# Sheet1.net
KiCad netlist of a schematic drawn in Altium Designer
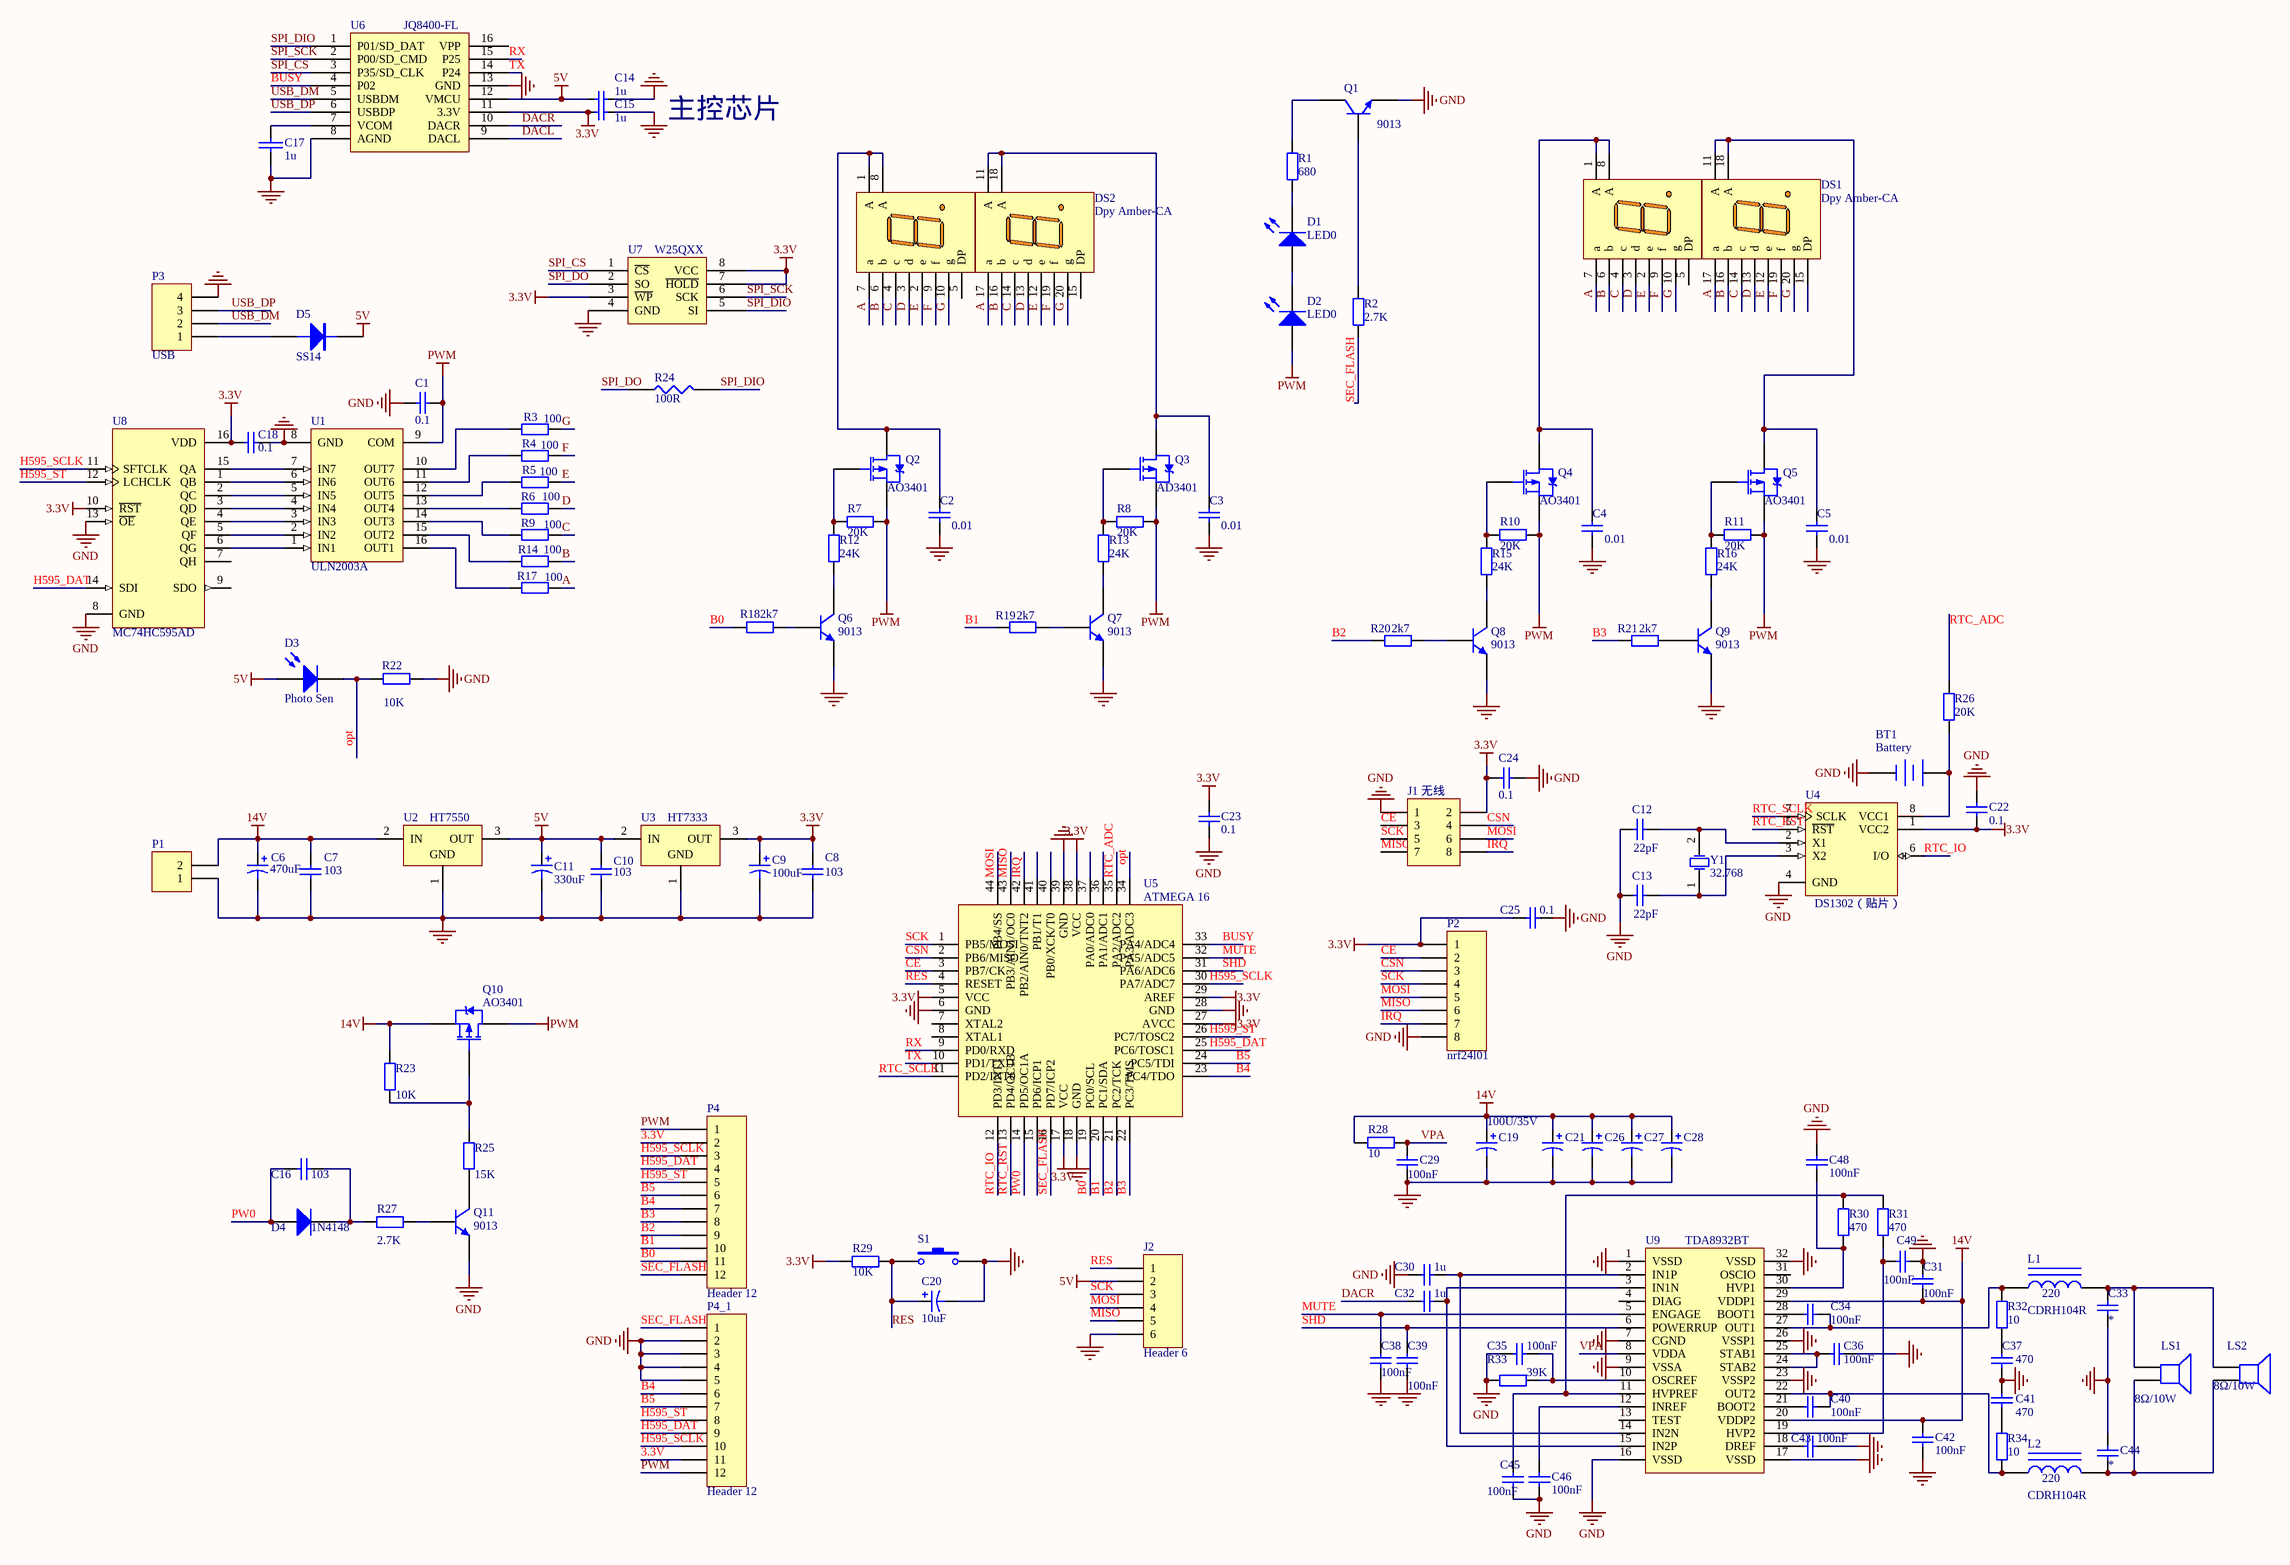
[diagram p0: Sheet1.SchDoc]

(export (version "E")
  (design (tool "Eeschema 10.0.6"))
  (components
    (comp (ref "BT1")
      (value "Battery")
      (footprint "1220电池底座")
      (description "Multicell Battery")
      (fields (field (name "PUBLISHER") "Altium Limited"))
      (libsource (lib "Miscellaneous Devices") (part "Battery"))
    )
    (comp (ref "C1")
      (value "0.1")
      (footprint "0805")
      (description "Capacitor")
      (fields (field (name "PUBLISHER") "Altium Limited"))
      (libsource (lib "Miscellaneous Devices") (part "Cap"))
    )
    (comp (ref "C2")
      (value "0.01")
      (footprint "0805")
      (description "Capacitor")
      (fields (field (name "Comment") "0.1") (field (name "PUBLISHER") "Altium Limited"))
      (libsource (lib "Miscellaneous Devices") (part "Cap"))
    )
    (comp (ref "C3")
      (value "0.01")
      (footprint "0805")
      (description "Capacitor")
      (fields (field (name "Comment") "0.1") (field (name "PUBLISHER") "Altium Limited"))
      (libsource (lib "Miscellaneous Devices") (part "Cap"))
    )
    (comp (ref "C4")
      (value "0.01")
      (footprint "0805")
      (description "Capacitor")
      (fields (field (name "Comment") "0.1") (field (name "PUBLISHER") "Altium Limited"))
      (libsource (lib "Miscellaneous Devices") (part "Cap"))
    )
    (comp (ref "C5")
      (value "0.01")
      (footprint "0805")
      (description "Capacitor")
      (fields (field (name "Comment") "0.1") (field (name "PUBLISHER") "Altium Limited"))
      (libsource (lib "Miscellaneous Devices") (part "Cap"))
    )
    (comp (ref "C6")
      (value "470uF")
      (footprint "470uf35V贴片")
      (description "Polarized Capacitor (Radial)")
      (fields (field (name "Comment") "Cap Pol1") (field (name "PUBLISHER") "Altium Limited"))
      (libsource (lib "Miscellaneous Devices") (part "Cap Pol1"))
    )
    (comp (ref "C7")
      (value "103")
      (footprint "0805")
      (description "Capacitor (Semiconductor SIM Model)")
      (fields (field (name "Comment") "Cap Semi") (field (name "PUBLISHER") "Altium Limited"))
      (libsource (lib "Miscellaneous Devices") (part "Cap Semi"))
    )
    (comp (ref "C8")
      (value "103")
      (footprint "0805")
      (description "Capacitor (Semiconductor SIM Model)")
      (fields (field (name "Comment") "Cap Semi") (field (name "PUBLISHER") "Altium Limited"))
      (libsource (lib "Miscellaneous Devices") (part "Cap Semi"))
    )
    (comp (ref "C9")
      (value "100uF")
      (footprint "1206")
      (description "Polarized Capacitor (Radial)")
      (fields (field (name "Comment") "Cap Pol1") (field (name "PUBLISHER") "Altium Limited"))
      (libsource (lib "Miscellaneous Devices") (part "Cap Pol1"))
    )
    (comp (ref "C10")
      (value "103")
      (footprint "0805")
      (description "Capacitor (Semiconductor SIM Model)")
      (fields (field (name "Comment") "Cap Semi") (field (name "PUBLISHER") "Altium Limited"))
      (libsource (lib "Miscellaneous Devices") (part "Cap Semi"))
    )
    (comp (ref "C11")
      (value "330uF")
      (footprint "220uf16V贴片")
      (description "Polarized Capacitor (Radial)")
      (fields (field (name "Comment") "Cap Pol1") (field (name "PUBLISHER") "Altium Limited"))
      (libsource (lib "Miscellaneous Devices") (part "Cap Pol1"))
    )
    (comp (ref "C12")
      (value "22pF")
      (footprint "0805")
      (description "Capacitor")
      (fields (field (name "Comment") "Cap") (field (name "PUBLISHER") "Altium Limited"))
      (libsource (lib "Miscellaneous Devices") (part "Cap"))
    )
    (comp (ref "C13")
      (value "22pF")
      (footprint "0805")
      (description "Capacitor")
      (fields (field (name "Comment") "Cap") (field (name "PUBLISHER") "Altium Limited"))
      (libsource (lib "Miscellaneous Devices") (part "Cap"))
    )
    (comp (ref "C14")
      (value "1u")
      (footprint "0805")
      (description "Capacitor")
      (libsource (lib "*") (part "CAP"))
    )
    (comp (ref "C15")
      (value "1u")
      (footprint "0805")
      (description "Capacitor")
      (libsource (lib "*") (part "CAP"))
    )
    (comp (ref "C16")
      (value "103")
      (footprint "0805")
      (description "Capacitor (Semiconductor SIM Model)")
      (fields (field (name "Comment") "Cap Semi") (field (name "PUBLISHER") "Altium Limited"))
      (libsource (lib "Miscellaneous Devices") (part "Cap Semi"))
    )
    (comp (ref "C17")
      (value "1u")
      (footprint "0805")
      (description "Capacitor")
      (libsource (lib "") (part "CAP_1"))
    )
    (comp (ref "C18")
      (value "0.1")
      (footprint "0805")
      (description "Capacitor")
      (fields (field (name "PUBLISHER") "Altium Limited"))
      (libsource (lib "Miscellaneous Devices") (part "Cap"))
    )
    (comp (ref "C19")
      (value "100U/35V")
      (footprint "220uf16V贴片")
      (description "Polarized Capacitor (Radial)")
      (fields (field (name "PUBLISHER") "Altium Limited"))
      (libsource (lib "Miscellaneous Devices") (part "Cap Pol1"))
    )
    (comp (ref "C20")
      (value "10uF")
      (footprint "1206")
      (description "Polarized Capacitor (Surface Mount)")
      (fields (field (name "PUBLISHER") "Altium Limited"))
      (libsource (lib "Miscellaneous Devices") (part "Cap Pol3"))
    )
    (comp (ref "C21")
      (value "Cap Pol1")
      (footprint "220uf16V贴片")
      (description "Polarized Capacitor (Radial)")
      (fields (field (name "PUBLISHER") "Altium Limited"))
      (libsource (lib "Miscellaneous Devices") (part "Cap Pol1"))
    )
    (comp (ref "C22")
      (value "0.1")
      (footprint "0805")
      (description "Capacitor")
      (fields (field (name "PUBLISHER") "Altium Limited"))
      (libsource (lib "Miscellaneous Devices") (part "Cap"))
    )
    (comp (ref "C23")
      (value "0.1")
      (footprint "0805")
      (description "Capacitor")
      (fields (field (name "PUBLISHER") "Altium Limited"))
      (libsource (lib "Miscellaneous Devices") (part "Cap"))
    )
    (comp (ref "C24")
      (value "0.1")
      (footprint "0805")
      (description "Capacitor")
      (fields (field (name "PUBLISHER") "Altium Limited"))
      (libsource (lib "Miscellaneous Devices") (part "Cap"))
    )
    (comp (ref "C25")
      (value "0.1")
      (footprint "0805")
      (description "Capacitor")
      (fields (field (name "PUBLISHER") "Altium Limited"))
      (libsource (lib "Miscellaneous Devices") (part "Cap"))
    )
    (comp (ref "C26")
      (value "Cap Pol1")
      (footprint "220uf16V贴片")
      (description "Polarized Capacitor (Radial)")
      (fields (field (name "PUBLISHER") "Altium Limited"))
      (libsource (lib "Miscellaneous Devices") (part "Cap Pol1"))
    )
    (comp (ref "C27")
      (value "Cap Pol1")
      (footprint "220uf16V贴片")
      (description "Polarized Capacitor (Radial)")
      (fields (field (name "PUBLISHER") "Altium Limited"))
      (libsource (lib "Miscellaneous Devices") (part "Cap Pol1"))
    )
    (comp (ref "C28")
      (value "Cap Pol1")
      (footprint "220uf16V贴片")
      (description "Polarized Capacitor (Radial)")
      (fields (field (name "PUBLISHER") "Altium Limited"))
      (libsource (lib "Miscellaneous Devices") (part "Cap Pol1"))
    )
    (comp (ref "C29")
      (value "100nF")
      (footprint "0603")
      (description "Capacitor")
      (fields (field (name "Comment") "0.1") (field (name "PUBLISHER") "Altium Limited"))
      (libsource (lib "Miscellaneous Devices") (part "Cap"))
    )
    (comp (ref "C30")
      (value "1u")
      (footprint "0603")
      (description "Capacitor")
      (fields (field (name "Comment") "0.1") (field (name "PUBLISHER") "Altium Limited"))
      (libsource (lib "Miscellaneous Devices") (part "Cap"))
    )
    (comp (ref "C31")
      (value "100nF")
      (footprint "0603")
      (description "Capacitor")
      (fields (field (name "Comment") "0.1") (field (name "PUBLISHER") "Altium Limited"))
      (libsource (lib "Miscellaneous Devices") (part "Cap"))
    )
    (comp (ref "C32")
      (value "1u")
      (footprint "0603")
      (description "Capacitor")
      (fields (field (name "Comment") "0.1") (field (name "PUBLISHER") "Altium Limited"))
      (libsource (lib "Miscellaneous Devices") (part "Cap"))
    )
    (comp (ref "C33")
      (value "0.1")
      (footprint "0805")
      (description "Capacitor")
      (fields (field (name "ALTIUM_VALUE") "*") (field (name "PUBLISHER") "Altium Limited"))
      (libsource (lib "Miscellaneous Devices") (part "Cap"))
    )
    (comp (ref "C34")
      (value "100nF")
      (footprint "0603")
      (description "Capacitor")
      (fields (field (name "Comment") "0.1") (field (name "PUBLISHER") "Altium Limited"))
      (libsource (lib "Miscellaneous Devices") (part "Cap"))
    )
    (comp (ref "C35")
      (value "100nF")
      (footprint "0603")
      (description "Capacitor")
      (fields (field (name "Comment") "0.1") (field (name "PUBLISHER") "Altium Limited"))
      (libsource (lib "Miscellaneous Devices") (part "Cap"))
    )
    (comp (ref "C36")
      (value "100nF")
      (footprint "0603")
      (description "Capacitor")
      (fields (field (name "Comment") "0.1") (field (name "PUBLISHER") "Altium Limited"))
      (libsource (lib "Miscellaneous Devices") (part "Cap"))
    )
    (comp (ref "C37")
      (value "470")
      (footprint "0603")
      (description "Capacitor")
      (fields (field (name "Comment") "0.1") (field (name "PUBLISHER") "Altium Limited"))
      (libsource (lib "Miscellaneous Devices") (part "Cap"))
    )
    (comp (ref "C38")
      (value "100nF")
      (footprint "0603")
      (description "Capacitor")
      (fields (field (name "Comment") "0.1") (field (name "PUBLISHER") "Altium Limited"))
      (libsource (lib "Miscellaneous Devices") (part "Cap"))
    )
    (comp (ref "C39")
      (value "100nF")
      (footprint "0603")
      (description "Capacitor")
      (fields (field (name "Comment") "0.1") (field (name "PUBLISHER") "Altium Limited"))
      (libsource (lib "Miscellaneous Devices") (part "Cap"))
    )
    (comp (ref "C40")
      (value "100nF")
      (footprint "0603")
      (description "Capacitor")
      (fields (field (name "Comment") "0.1") (field (name "PUBLISHER") "Altium Limited"))
      (libsource (lib "Miscellaneous Devices") (part "Cap"))
    )
    (comp (ref "C41")
      (value "470")
      (footprint "0603")
      (description "Capacitor")
      (fields (field (name "Comment") "0.1") (field (name "PUBLISHER") "Altium Limited"))
      (libsource (lib "Miscellaneous Devices") (part "Cap"))
    )
    (comp (ref "C42")
      (value "100nF")
      (footprint "0603")
      (description "Capacitor")
      (fields (field (name "Comment") "0.1") (field (name "PUBLISHER") "Altium Limited"))
      (libsource (lib "Miscellaneous Devices") (part "Cap"))
    )
    (comp (ref "C43")
      (value "100nF")
      (footprint "0603")
      (description "Capacitor")
      (fields (field (name "Comment") "0.1") (field (name "PUBLISHER") "Altium Limited"))
      (libsource (lib "Miscellaneous Devices") (part "Cap"))
    )
    (comp (ref "C44")
      (value "0.1")
      (footprint "0805")
      (description "Capacitor")
      (fields (field (name "ALTIUM_VALUE") "*") (field (name "PUBLISHER") "Altium Limited"))
      (libsource (lib "Miscellaneous Devices") (part "Cap"))
    )
    (comp (ref "C45")
      (value "100nF")
      (footprint "0603")
      (description "Capacitor")
      (fields (field (name "Comment") "0.1") (field (name "PUBLISHER") "Altium Limited"))
      (libsource (lib "Miscellaneous Devices") (part "Cap"))
    )
    (comp (ref "C46")
      (value "100nF")
      (footprint "0603")
      (description "Capacitor")
      (fields (field (name "Comment") "0.1") (field (name "PUBLISHER") "Altium Limited"))
      (libsource (lib "Miscellaneous Devices") (part "Cap"))
    )
    (comp (ref "C48")
      (value "100nF")
      (footprint "0603")
      (description "Capacitor")
      (fields (field (name "Comment") "0.1") (field (name "PUBLISHER") "Altium Limited"))
      (libsource (lib "Miscellaneous Devices") (part "Cap"))
    )
    (comp (ref "C49")
      (value "100nF")
      (footprint "0603")
      (description "Capacitor")
      (fields (field (name "Comment") "0.1") (field (name "PUBLISHER") "Altium Limited"))
      (libsource (lib "Miscellaneous Devices") (part "Cap"))
    )
    (comp (ref "D1")
      (value "LED0")
      (footprint "led")
      (description "Typical INFRARED GaAs LED")
      (fields (field (name "PUBLISHER") "Altium Limited"))
      (libsource (lib "Miscellaneous Devices") (part "LED0"))
    )
    (comp (ref "D2")
      (value "LED0")
      (footprint "led")
      (description "Typical INFRARED GaAs LED")
      (fields (field (name "PUBLISHER") "Altium Limited"))
      (libsource (lib "Miscellaneous Devices") (part "LED0"))
    )
    (comp (ref "D3")
      (value "Photo Sen")
      (footprint "2排针")
      (description "Photosensitive Diode")
      (fields (field (name "PUBLISHER") "Altium Limited"))
      (libsource (lib "Miscellaneous Devices") (part "Photo Sen"))
    )
    (comp (ref "D4")
      (value "1N4148")
      (footprint "1206")
      (description "1 Amp General Purpose Rectifier")
      (fields (field (name "PUBLISHER") "Altium Limited"))
      (libsource (lib "Miscellaneous Devices") (part "Diode 1N4007"))
    )
    (comp (ref "D5")
      (value "SS14")
      (footprint "1206")
      (description "Diode")
      (libsource (lib "*") (part "DIODE"))
    )
    (comp (ref "DS1")
      (value "Dpy Amber-CA")
      (footprint "5英寸数码管")
      (description "7.62 mm Black Surface Orange 7-Segment Display: CA, RH DP")
      (fields (field (name "PUBLISHER") "Altium Limited"))
      (libsource (lib "PCB_Project1") (part "Dpy Amber-CA"))
    )
    (comp (ref "DS2")
      (value "Dpy Amber-CA")
      (footprint "5英寸数码管")
      (description "7.62 mm Black Surface Orange 7-Segment Display: CA, RH DP")
      (fields (field (name "PUBLISHER") "Altium Limited"))
      (libsource (lib "PCB_Project1") (part "Dpy Amber-CA"))
    )
    (comp (ref "J1")
      (value "无线")
      (footprint "无线模块")
      (description "Header, 4-Pin, Dual row")
      (fields (field (name "PUBLISHER") "Altium Limited"))
      (libsource (lib "Miscellaneous Connectors") (part "Header 4X2"))
    )
    (comp (ref "J2")
      (value "Header 6")
      (footprint "HDR1X6")
      (description "Header, 6-Pin")
      (fields (field (name "PUBLISHER") "Altium Limited"))
      (libsource (lib "Miscellaneous Connectors") (part "Header 6"))
    )
    (comp (ref "L1")
      (value "220")
      (footprint "CDRH104")
      (description "Magnetic-Core Inductor")
      (fields (field (name "ALTIUM_VALUE") "CDRH104R") (field (name "PUBLISHER") "Altium Limited"))
      (libsource (lib "Miscellaneous Devices") (part "Inductor Iron"))
    )
    (comp (ref "L2")
      (value "220")
      (footprint "CDRH104")
      (description "Magnetic-Core Inductor")
      (fields (field (name "ALTIUM_VALUE") "CDRH104R") (field (name "PUBLISHER") "Altium Limited"))
      (libsource (lib "Miscellaneous Devices") (part "Inductor Iron"))
    )
    (comp (ref "LS1")
      (value "8Ω/10W")
      (footprint "2排针")
      (description "Loudspeaker")
      (fields (field (name "PUBLISHER") "Altium Limited"))
      (libsource (lib "Miscellaneous Devices") (part "Speaker"))
    )
    (comp (ref "LS2")
      (value "8Ω/10W")
      (footprint "2排针")
      (description "Loudspeaker")
      (fields (field (name "PUBLISHER") "Altium Limited"))
      (libsource (lib "Miscellaneous Devices") (part "Speaker"))
    )
    (comp (ref "P1")
      (value "Header 2")
      (footprint "电源插头")
      (description "Header, 2-Pin")
      (fields (field (name "PUBLISHER") "Altium Limited"))
      (libsource (lib "Miscellaneous Connectors") (part "Header 2"))
    )
    (comp (ref "P2")
      (value "nrf24l01")
      (footprint "24L01")
      (description "Header, 8-Pin")
      (fields (field (name "PUBLISHER") "Altium Limited"))
      (libsource (lib "Miscellaneous Connectors") (part "Header 8"))
    )
    (comp (ref "P3")
      (value "USB")
      (footprint "HDR1X4")
      (description "Header, 4-Pin")
      (fields (field (name "PUBLISHER") "Altium Limited"))
      (libsource (lib "Miscellaneous Connectors") (part "Header 4"))
    )
    (comp (ref "P4")
      (value "Header 12")
      (footprint "FPC-12P1MM")
      (description "Header, 12-Pin")
      (fields (field (name "PUBLISHER") "Altium Limited"))
      (libsource (lib "Miscellaneous Connectors") (part "Header 12"))
    )
    (comp (ref "P4_1")
      (value "Header 12")
      (footprint "FPC-12P1MM")
      (description "Header, 12-Pin")
      (fields (field (name "PUBLISHER") "Altium Limited"))
      (libsource (lib "Miscellaneous Connectors") (part "Header 12"))
    )
    (comp (ref "Q1")
      (value "9013")
      (footprint "9013贴片（专用）")
      (description "NPN General Purpose Amplifier")
      (fields (field (name "PUBLISHER") "Altium Limited"))
      (libsource (lib "") (part "2N3904_1"))
    )
    (comp (ref "Q2")
      (value "AO3401")
      (footprint "SOP-23")
      (description "P-Channel Power MOSFET")
      (fields (field (name "PUBLISHER") "Altium Limited"))
      (libsource (lib "Miscellaneous Devices") (part "PMOS-2"))
    )
    (comp (ref "Q3")
      (value "AD3401")
      (footprint "SOP-23")
      (description "P-Channel Power MOSFET")
      (fields (field (name "PUBLISHER") "Altium Limited"))
      (libsource (lib "Miscellaneous Devices") (part "PMOS-2"))
    )
    (comp (ref "Q4")
      (value "AO3401")
      (footprint "SOP-23")
      (description "P-Channel Power MOSFET")
      (fields (field (name "PUBLISHER") "Altium Limited"))
      (libsource (lib "Miscellaneous Devices") (part "PMOS-2"))
    )
    (comp (ref "Q5")
      (value "AO3401")
      (footprint "SOP-23")
      (description "P-Channel Power MOSFET")
      (fields (field (name "PUBLISHER") "Altium Limited"))
      (libsource (lib "Miscellaneous Devices") (part "PMOS-2"))
    )
    (comp (ref "Q6")
      (value "9013")
      (footprint "9013贴片（专用）")
      (description "NPN General Purpose Amplifier")
      (fields (field (name "PUBLISHER") "Altium Limited"))
      (libsource (lib "Miscellaneous Devices") (part "2N3904"))
    )
    (comp (ref "Q7")
      (value "9013")
      (footprint "9013贴片（专用）")
      (description "NPN General Purpose Amplifier")
      (fields (field (name "PUBLISHER") "Altium Limited"))
      (libsource (lib "Miscellaneous Devices") (part "2N3904"))
    )
    (comp (ref "Q8")
      (value "9013")
      (footprint "9013贴片（专用）")
      (description "NPN General Purpose Amplifier")
      (fields (field (name "PUBLISHER") "Altium Limited"))
      (libsource (lib "Miscellaneous Devices") (part "2N3904"))
    )
    (comp (ref "Q9")
      (value "9013")
      (footprint "9013贴片（专用）")
      (description "NPN General Purpose Amplifier")
      (fields (field (name "PUBLISHER") "Altium Limited"))
      (libsource (lib "Miscellaneous Devices") (part "2N3904"))
    )
    (comp (ref "Q10")
      (value "AO3401")
      (footprint "SOP-23")
      (description "P-Channel Power MOSFET")
      (fields (field (name "PUBLISHER") "Altium Limited"))
      (libsource (lib "") (part "PMOS-2_1"))
    )
    (comp (ref "Q11")
      (value "9013")
      (footprint "9013贴片（专用）")
      (description "NPN General Purpose Amplifier")
      (fields (field (name "PUBLISHER") "Altium Limited"))
      (libsource (lib "") (part "2N3904_1"))
    )
    (comp (ref "R1")
      (value "680")
      (footprint "0805")
      (description "Resistor")
      (fields (field (name "Comment") "Res2") (field (name "PUBLISHER") "Altium Limited"))
      (libsource (lib "Miscellaneous Devices") (part "Res2"))
    )
    (comp (ref "R2")
      (value "2.7K")
      (footprint "0805")
      (description "Resistor")
      (fields (field (name "Comment") "Res2") (field (name "PUBLISHER") "Altium Limited"))
      (libsource (lib "Miscellaneous Devices") (part "Res2"))
    )
    (comp (ref "R3")
      (value "100")
      (footprint "0805")
      (description "Resistor")
      (fields (field (name "PUBLISHER") "Altium Limited"))
      (libsource (lib "") (part "Res2_2"))
    )
    (comp (ref "R4")
      (value "100")
      (footprint "0805")
      (description "Resistor")
      (fields (field (name "PUBLISHER") "Altium Limited"))
      (libsource (lib "") (part "Res2_2"))
    )
    (comp (ref "R5")
      (value "100")
      (footprint "0805")
      (description "Resistor")
      (fields (field (name "PUBLISHER") "Altium Limited"))
      (libsource (lib "") (part "Res2_2"))
    )
    (comp (ref "R6")
      (value "100")
      (footprint "0805")
      (description "Resistor")
      (fields (field (name "PUBLISHER") "Altium Limited"))
      (libsource (lib "") (part "Res2_2"))
    )
    (comp (ref "R7")
      (value "20K")
      (footprint "0805")
      (description "Resistor")
      (fields (field (name "PUBLISHER") "Altium Limited"))
      (libsource (lib "") (part "Res2_1"))
    )
    (comp (ref "R8")
      (value "20K")
      (footprint "0805")
      (description "Resistor")
      (fields (field (name "PUBLISHER") "Altium Limited"))
      (libsource (lib "") (part "Res2_1"))
    )
    (comp (ref "R9")
      (value "100")
      (footprint "0805")
      (description "Resistor")
      (fields (field (name "PUBLISHER") "Altium Limited"))
      (libsource (lib "") (part "Res2_2"))
    )
    (comp (ref "R10")
      (value "20K")
      (footprint "0805")
      (description "Resistor")
      (fields (field (name "PUBLISHER") "Altium Limited"))
      (libsource (lib "") (part "Res2_1"))
    )
    (comp (ref "R11")
      (value "20K")
      (footprint "0805")
      (description "Resistor")
      (fields (field (name "PUBLISHER") "Altium Limited"))
      (libsource (lib "") (part "Res2_1"))
    )
    (comp (ref "R12")
      (value "24K")
      (footprint "0805")
      (description "Resistor")
      (fields (field (name "PUBLISHER") "Altium Limited"))
      (libsource (lib "") (part "Res2_4"))
    )
    (comp (ref "R13")
      (value "24K")
      (footprint "0603")
      (description "Resistor")
      (fields (field (name "PUBLISHER") "Altium Limited"))
      (libsource (lib "") (part "Res2_4"))
    )
    (comp (ref "R14")
      (value "100")
      (footprint "0805")
      (description "Resistor")
      (fields (field (name "PUBLISHER") "Altium Limited"))
      (libsource (lib "") (part "Res2_2"))
    )
    (comp (ref "R15")
      (value "24K")
      (footprint "0805")
      (description "Resistor")
      (fields (field (name "PUBLISHER") "Altium Limited"))
      (libsource (lib "") (part "Res2_4"))
    )
    (comp (ref "R16")
      (value "24K")
      (footprint "0805")
      (description "Resistor")
      (fields (field (name "PUBLISHER") "Altium Limited"))
      (libsource (lib "") (part "Res2_4"))
    )
    (comp (ref "R17")
      (value "100")
      (footprint "0805")
      (description "Resistor")
      (fields (field (name "PUBLISHER") "Altium Limited"))
      (libsource (lib "") (part "Res2_2"))
    )
    (comp (ref "R18")
      (value "2k7")
      (footprint "0805")
      (description "Resistor")
      (fields (field (name "PUBLISHER") "Altium Limited"))
      (libsource (lib "") (part "Res2_2"))
    )
    (comp (ref "R19")
      (value "2k7")
      (footprint "0805")
      (description "Resistor")
      (fields (field (name "PUBLISHER") "Altium Limited"))
      (libsource (lib "") (part "Res2_2"))
    )
    (comp (ref "R20")
      (value "2k7")
      (footprint "0805")
      (description "Resistor")
      (fields (field (name "PUBLISHER") "Altium Limited"))
      (libsource (lib "") (part "Res2_2"))
    )
    (comp (ref "R21")
      (value "2k7")
      (footprint "0805")
      (description "Resistor")
      (fields (field (name "PUBLISHER") "Altium Limited"))
      (libsource (lib "") (part "Res2_2"))
    )
    (comp (ref "R22")
      (value "10K")
      (footprint "0805")
      (description "Resistor")
      (fields (field (name "PUBLISHER") "Altium Limited"))
      (libsource (lib "") (part "Res2_6"))
    )
    (comp (ref "R23")
      (value "10K")
      (footprint "0805")
      (description "Resistor")
      (fields (field (name "Comment") "Res2") (field (name "PUBLISHER") "Altium Limited"))
      (libsource (lib "Miscellaneous Devices") (part "Res2"))
    )
    (comp (ref "R24") (value "100R") (libsource (lib "*") (part "RES1")))
    (comp (ref "R25")
      (value "15K")
      (footprint "0805")
      (description "Resistor")
      (fields (field (name "Comment") "Res2") (field (name "PUBLISHER") "Altium Limited"))
      (libsource (lib "Miscellaneous Devices") (part "Res2"))
    )
    (comp (ref "R26")
      (value "20K")
      (footprint "0805")
      (description "Resistor")
      (fields (field (name "PUBLISHER") "Altium Limited"))
      (libsource (lib "") (part "Res2_4"))
    )
    (comp (ref "R27")
      (value "2.7K")
      (footprint "0805")
      (description "Resistor")
      (fields (field (name "Comment") "Res2") (field (name "PUBLISHER") "Altium Limited"))
      (libsource (lib "") (part "Res2_6"))
    )
    (comp (ref "R28")
      (value "10")
      (footprint "0805")
      (description "Resistor")
      (fields (field (name "PUBLISHER") "Altium Limited"))
      (libsource (lib "Miscellaneous Devices") (part "Res2"))
    )
    (comp (ref "R29")
      (value "10K")
      (footprint "0805")
      (description "Resistor")
      (fields (field (name "PUBLISHER") "Altium Limited"))
      (libsource (lib "") (part "Res2_3"))
    )
    (comp (ref "R30")
      (value "470")
      (footprint "0603")
      (description "Resistor")
      (fields (field (name "PUBLISHER") "Altium Limited"))
      (libsource (lib "") (part "Res2_4"))
    )
    (comp (ref "R31")
      (value "470")
      (footprint "0603")
      (description "Resistor")
      (fields (field (name "PUBLISHER") "Altium Limited"))
      (libsource (lib "") (part "Res2_4"))
    )
    (comp (ref "R32")
      (value "10")
      (footprint "0603")
      (description "Resistor")
      (fields (field (name "PUBLISHER") "Altium Limited"))
      (libsource (lib "") (part "Res2_4"))
    )
    (comp (ref "R33")
      (value "39K")
      (footprint "0603")
      (description "Resistor")
      (fields (field (name "PUBLISHER") "Altium Limited"))
      (libsource (lib "") (part "Res2_1"))
    )
    (comp (ref "R34")
      (value "10")
      (footprint "0603")
      (description "Resistor")
      (fields (field (name "PUBLISHER") "Altium Limited"))
      (libsource (lib "") (part "Res2_5"))
    )
    (comp (ref "S1")
      (value "~")
      (footprint "4脚按键")
      (description "Switch")
      (fields (field (name "PUBLISHER") "Altium Limited"))
      (libsource (lib "Miscellaneous Devices") (part "SW-PB"))
    )
    (comp (ref "U1")
      (value "ULN2003A")
      (footprint "SO-16")
      (description "High-Voltage, High-Current Darlington Array")
      (fields (field (name "PUBLISHER") "Altium Limited"))
      (libsource (lib "Allegro Interface Darlington Driver") (part "ULN2003A"))
    )
    (comp (ref "U2")
      (value "HT7550")
      (footprint "SOT89L")
      (description "3.0V 100mA Low Power,  Low Dropout Voltage (LDO) Regulator")
      (fields (field (name "PUBLISHER") "Altium Limited"))
      (libsource (lib "Holtek Power Mgt Voltage Regulator") (part "HT7530-1"))
    )
    (comp (ref "U3")
      (value "HT7333")
      (footprint "SOT89L")
      (description "3.0V 100mA Low Power,  Low Dropout Voltage (LDO) Regulator")
      (fields (field (name "PUBLISHER") "Altium Limited"))
      (libsource (lib "Holtek Power Mgt Voltage Regulator") (part "HT7530-1"))
    )
    (comp (ref "U4")
      (value "DS1302（贴片）")
      (footprint "SOP8（DS1302）")
      (description "Trickle Charge Timekeeping Chip")
      (fields (field (name "PUBLISHER") "Altium Limited"))
      (libsource (lib "Dallas Peripheral Real Time Clock") (part "DS1302"))
    )
    (comp (ref "U5")
      (value "ATMEGA 16")
      (footprint "44贴片（顶层）")
      (libsource (lib "AVR最小系统") (part "ATMEGA 16"))
    )
    (comp (ref "U6") (value "JQ8400-FL") (footprint "SO-16") (libsource (lib "*") (part "W6082")))
    (comp (ref "U7") (value "W25QXX") (footprint "w25") (libsource (lib "*") (part "W25QXX")))
    (comp (ref "U8")
      (value "MC74HC595AD")
      (footprint "751B-05_N")
      (description "8-Bit Serial-Input/Serial or Prallel-Output Shift Register with Latched 3-State Outputs")
      (fields (field (name "PUBLISHER") "Altium Limited"))
      (libsource (lib "ON Semi Logic Register") (part "MC74HC595AD"))
    )
    (comp (ref "U9")
      (value "TDA8932BT")
      (footprint "SOIC127P1047-32L")
      (libsource (lib "PCB_Project1") (part "TDA8932"))
    )
    (comp (ref "Y1")
      (value "32.768")
      (footprint "32K")
      (description "Crystal Oscillator")
      (fields (field (name "PUBLISHER") "Altium Limited"))
      (libsource (lib "Miscellaneous Devices") (part "XTAL"))
    )
  )
  (nets
    (net (code "1") (name "/A") (class "Default")
      (node (ref "DS1") (pin "17") (pinfunction "a_17") (pintype "passive"))
      (node (ref "DS1") (pin "7") (pinfunction "a_7") (pintype "passive"))
      (node (ref "DS2") (pin "17") (pinfunction "a_17") (pintype "passive"))
      (node (ref "DS2") (pin "7") (pinfunction "a_7") (pintype "passive"))
      (node (ref "R17") (pin "1") (pinfunction "1_1") (pintype "passive"))
    )
    (net (code "2") (name "/B") (class "Default")
      (node (ref "DS1") (pin "16") (pinfunction "b_16") (pintype "passive"))
      (node (ref "DS1") (pin "6") (pinfunction "b_6") (pintype "passive"))
      (node (ref "DS2") (pin "16") (pinfunction "b_16") (pintype "passive"))
      (node (ref "DS2") (pin "6") (pinfunction "b_6") (pintype "passive"))
      (node (ref "R14") (pin "1") (pinfunction "1_1") (pintype "passive"))
    )
    (net (code "3") (name "/B0") (class "Default")
      (node (ref "P4") (pin "11") (pinfunction "11_11") (pintype "passive"))
      (node (ref "R18") (pin "2") (pinfunction "2_2") (pintype "passive"))
      (node (ref "U5") (pin "19") (pinfunction "PC0/SCL_19") (pintype "passive"))
    )
    (net (code "4") (name "/B1") (class "Default")
      (node (ref "P4") (pin "10") (pinfunction "10_10") (pintype "passive"))
      (node (ref "R19") (pin "2") (pinfunction "2_2") (pintype "passive"))
      (node (ref "U5") (pin "20") (pinfunction "PC1/SDA_20") (pintype "passive"))
    )
    (net (code "5") (name "/B2") (class "Default")
      (node (ref "P4") (pin "9") (pinfunction "9_9") (pintype "passive"))
      (node (ref "R20") (pin "2") (pinfunction "2_2") (pintype "passive"))
      (node (ref "U5") (pin "21") (pinfunction "PC2/TCK_21") (pintype "passive"))
    )
    (net (code "6") (name "/B3") (class "Default")
      (node (ref "P4") (pin "8") (pinfunction "8_8") (pintype "passive"))
      (node (ref "R21") (pin "2") (pinfunction "2_2") (pintype "passive"))
      (node (ref "U5") (pin "22") (pinfunction "PC3/TMS_22") (pintype "passive"))
    )
    (net (code "7") (name "/B4") (class "Default")
      (node (ref "P4") (pin "7") (pinfunction "7_7") (pintype "passive"))
      (node (ref "P4_1") (pin "6") (pinfunction "6_6") (pintype "passive"))
      (node (ref "U5") (pin "23") (pinfunction "PC4/TDO_23") (pintype "passive"))
    )
    (net (code "8") (name "/B5") (class "Default")
      (node (ref "P4") (pin "6") (pinfunction "6_6") (pintype "passive"))
      (node (ref "P4_1") (pin "7") (pinfunction "7_7") (pintype "passive"))
      (node (ref "U5") (pin "24") (pinfunction "PC5/TDI_24") (pintype "passive"))
    )
    (net (code "9") (name "/BUSY") (class "Default")
      (node (ref "U5") (pin "33") (pinfunction "PA4/ADC4_33") (pintype "passive"))
      (node (ref "U6") (pin "4") (pinfunction "P02_4") (pintype "passive"))
    )
    (net (code "10") (name "/C") (class "Default")
      (node (ref "DS1") (pin "14") (pinfunction "c_14") (pintype "passive"))
      (node (ref "DS1") (pin "4") (pinfunction "c_4") (pintype "passive"))
      (node (ref "DS2") (pin "14") (pinfunction "c_14") (pintype "passive"))
      (node (ref "DS2") (pin "4") (pinfunction "c_4") (pintype "passive"))
      (node (ref "R9") (pin "1") (pinfunction "1_1") (pintype "passive"))
    )
    (net (code "11") (name "/CE") (class "Default")
      (node (ref "J1") (pin "3") (pinfunction "3_3") (pintype "passive"))
      (node (ref "P2") (pin "2") (pinfunction "2_2") (pintype "passive"))
      (node (ref "U5") (pin "3") (pinfunction "PB7/CK_3") (pintype "passive"))
    )
    (net (code "12") (name "/CSN") (class "Default")
      (node (ref "J1") (pin "4") (pinfunction "4_4") (pintype "passive"))
      (node (ref "P2") (pin "3") (pinfunction "3_3") (pintype "passive"))
      (node (ref "U5") (pin "2") (pinfunction "PB6/MISO_2") (pintype "passive"))
    )
    (net (code "13") (name "/D") (class "Default")
      (node (ref "DS1") (pin "13") (pinfunction "d_13") (pintype "passive"))
      (node (ref "DS1") (pin "3") (pinfunction "d_3") (pintype "passive"))
      (node (ref "DS2") (pin "13") (pinfunction "d_13") (pintype "passive"))
      (node (ref "DS2") (pin "3") (pinfunction "d_3") (pintype "passive"))
      (node (ref "R6") (pin "1") (pinfunction "1_1") (pintype "passive"))
    )
    (net (code "14") (name "/DACL") (class "Default")
      (node (ref "U6") (pin "9") (pinfunction "DACL_9") (pintype "passive"))
    )
    (net (code "15") (name "/DACR") (class "Default")
      (node (ref "C32") (pin "1") (pinfunction "1_1") (pintype "passive"))
      (node (ref "U6") (pin "10") (pinfunction "DACR_10") (pintype "passive"))
    )
    (net (code "16") (name "/E") (class "Default")
      (node (ref "DS1") (pin "12") (pinfunction "e_12") (pintype "passive"))
      (node (ref "DS1") (pin "2") (pinfunction "e_2") (pintype "passive"))
      (node (ref "DS2") (pin "12") (pinfunction "e_12") (pintype "passive"))
      (node (ref "DS2") (pin "2") (pinfunction "e_2") (pintype "passive"))
      (node (ref "R5") (pin "1") (pinfunction "1_1") (pintype "passive"))
    )
    (net (code "17") (name "/F") (class "Default")
      (node (ref "DS1") (pin "19") (pinfunction "f_19") (pintype "passive"))
      (node (ref "DS1") (pin "9") (pinfunction "f_9") (pintype "passive"))
      (node (ref "DS2") (pin "19") (pinfunction "f_19") (pintype "passive"))
      (node (ref "DS2") (pin "9") (pinfunction "f_9") (pintype "passive"))
      (node (ref "R4") (pin "1") (pinfunction "1_1") (pintype "passive"))
    )
    (net (code "18") (name "/G") (class "Default")
      (node (ref "DS1") (pin "10") (pinfunction "g_10") (pintype "passive"))
      (node (ref "DS1") (pin "20") (pinfunction "g_20") (pintype "passive"))
      (node (ref "DS2") (pin "10") (pinfunction "g_10") (pintype "passive"))
      (node (ref "DS2") (pin "20") (pinfunction "g_20") (pintype "passive"))
      (node (ref "R3") (pin "1") (pinfunction "1_1") (pintype "passive"))
    )
    (net (code "19") (name "/H595_DAT") (class "Default")
      (node (ref "P4") (pin "4") (pinfunction "4_4") (pintype "passive"))
      (node (ref "P4_1") (pin "9") (pinfunction "9_9") (pintype "passive"))
      (node (ref "U5") (pin "25") (pinfunction "PC6/TOSC1_25") (pintype "passive"))
      (node (ref "U8") (pin "14") (pinfunction "SDI_14") (pintype "input"))
    )
    (net (code "20") (name "/H595_SCLK") (class "Default")
      (node (ref "P4") (pin "3") (pinfunction "3_3") (pintype "passive"))
      (node (ref "P4_1") (pin "10") (pinfunction "10_10") (pintype "passive"))
      (node (ref "U5") (pin "30") (pinfunction "PA7/ADC7_30") (pintype "passive"))
      (node (ref "U8") (pin "11") (pinfunction "SFTCLK_11") (pintype "input"))
    )
    (net (code "21") (name "/H595_ST") (class "Default")
      (node (ref "P4") (pin "5") (pinfunction "5_5") (pintype "passive"))
      (node (ref "P4_1") (pin "8") (pinfunction "8_8") (pintype "passive"))
      (node (ref "U5") (pin "26") (pinfunction "PC7/TOSC2_26") (pintype "passive"))
      (node (ref "U8") (pin "12") (pinfunction "LCHCLK_12") (pintype "input"))
    )
    (net (code "22") (name "/IRQ") (class "Default")
      (node (ref "J1") (pin "8") (pinfunction "8_8") (pintype "passive"))
      (node (ref "P2") (pin "7") (pinfunction "7_7") (pintype "passive"))
      (node (ref "U5") (pin "42") (pinfunction "PB2/AIN0/TNT2_42") (pintype "passive"))
    )
    (net (code "23") (name "/MISO") (class "Default")
      (node (ref "J1") (pin "7") (pinfunction "7_7") (pintype "passive"))
      (node (ref "J2") (pin "5") (pinfunction "5_5") (pintype "passive"))
      (node (ref "P2") (pin "6") (pinfunction "6_6") (pintype "passive"))
      (node (ref "U5") (pin "43") (pinfunction "PB3/AIN1/OC0_43") (pintype "passive"))
    )
    (net (code "24") (name "/MOSI") (class "Default")
      (node (ref "J1") (pin "6") (pinfunction "6_6") (pintype "passive"))
      (node (ref "J2") (pin "4") (pinfunction "4_4") (pintype "passive"))
      (node (ref "P2") (pin "5") (pinfunction "5_5") (pintype "passive"))
      (node (ref "U5") (pin "44") (pinfunction "PB4/SS_44") (pintype "passive"))
    )
    (net (code "25") (name "/MUTE") (class "Default")
      (node (ref "C38") (pin "2") (pinfunction "2_2") (pintype "passive"))
      (node (ref "U5") (pin "32") (pinfunction "PA5/ADC5_32") (pintype "passive"))
      (node (ref "U9") (pin "5") (pinfunction "ENGAGE_5") (pintype "passive"))
    )
    (net (code "26") (name "/PW0") (class "Default")
      (node (ref "C16") (pin "2") (pinfunction "2_2") (pintype "passive"))
      (node (ref "D4") (pin "1") (pinfunction "A_1") (pintype "passive"))
      (node (ref "U5") (pin "14") (pinfunction "PD5/OC1A_14") (pintype "passive"))
    )
    (net (code "27") (name "/RES") (class "Default")
      (node (ref "C20") (pin "1") (pinfunction "1_1") (pintype "passive"))
      (node (ref "J2") (pin "1") (pinfunction "1_1") (pintype "passive"))
      (node (ref "R29") (pin "2") (pinfunction "2_2") (pintype "passive"))
      (node (ref "S1") (pin "1") (pinfunction "1_1") (pintype "passive"))
      (node (ref "U5") (pin "4") (pinfunction "RESET_4") (pintype "passive"))
    )
    (net (code "28") (name "/RTC_ADC") (class "Default")
      (node (ref "R26") (pin "1") (pinfunction "1_1") (pintype "passive"))
      (node (ref "U5") (pin "35") (pinfunction "PA2/ADC2_35") (pintype "passive"))
    )
    (net (code "29") (name "/RTC_IO") (class "Default")
      (node (ref "U4") (pin "6") (pinfunction "I/O_6") (pintype "bidirectional"))
      (node (ref "U5") (pin "12") (pinfunction "PD3/INT1_12") (pintype "passive"))
    )
    (net (code "30") (name "/RTC_RST") (class "Default")
      (node (ref "U4") (pin "5") (pinfunction "~{RST}_5") (pintype "input"))
      (node (ref "U5") (pin "13") (pinfunction "PD4/OC1B_13") (pintype "passive"))
    )
    (net (code "31") (name "/RTC_SCLK") (class "Default")
      (node (ref "U4") (pin "7") (pinfunction "SCLK_7") (pintype "input"))
      (node (ref "U5") (pin "11") (pinfunction "PD2/INT0_11") (pintype "passive"))
    )
    (net (code "32") (name "/RX") (class "Default")
      (node (ref "U5") (pin "9") (pinfunction "PD0/RXD_9") (pintype "passive"))
      (node (ref "U6") (pin "15") (pinfunction "P25_15") (pintype "passive"))
    )
    (net (code "33") (name "/SCK") (class "Default")
      (node (ref "J1") (pin "5") (pinfunction "5_5") (pintype "passive"))
      (node (ref "J2") (pin "3") (pinfunction "3_3") (pintype "passive"))
      (node (ref "P2") (pin "4") (pinfunction "4_4") (pintype "passive"))
      (node (ref "U5") (pin "1") (pinfunction "PB5/MOSI_1") (pintype "passive"))
    )
    (net (code "34") (name "/SEC_FLASH") (class "Default")
      (node (ref "P4") (pin "12") (pinfunction "12_12") (pintype "passive"))
      (node (ref "P4_1") (pin "1") (pinfunction "1_1") (pintype "passive"))
      (node (ref "R2") (pin "1") (pinfunction "1_1") (pintype "passive"))
      (node (ref "U5") (pin "16") (pinfunction "PD7/ICP2_16") (pintype "passive"))
    )
    (net (code "35") (name "/SHD") (class "Default")
      (node (ref "C39") (pin "2") (pinfunction "2_2") (pintype "passive"))
      (node (ref "U5") (pin "31") (pinfunction "PA6/ADC6_31") (pintype "passive"))
      (node (ref "U9") (pin "6") (pinfunction "POWERRUP_6") (pintype "passive"))
    )
    (net (code "36") (name "/SPI_CS") (class "Default")
      (node (ref "U6") (pin "3") (pinfunction "P35/SD_CLK_3") (pintype "passive"))
      (node (ref "U7") (pin "1") (pinfunction "~{CS}_1") (pintype "passive"))
    )
    (net (code "37") (name "/SPI_DIO") (class "Default")
      (node (ref "R24") (pin "2") (pinfunction "2_2") (pintype "passive"))
      (node (ref "U6") (pin "1") (pinfunction "P01/SD_DAT_1") (pintype "passive"))
      (node (ref "U7") (pin "5") (pinfunction "SI_5") (pintype "passive"))
    )
    (net (code "38") (name "/SPI_DO") (class "Default")
      (node (ref "R24") (pin "1") (pinfunction "1_1") (pintype "passive"))
      (node (ref "U7") (pin "2") (pinfunction "SO_2") (pintype "passive"))
    )
    (net (code "39") (name "/SPI_SCK") (class "Default")
      (node (ref "U6") (pin "2") (pinfunction "P00/SD_CMD_2") (pintype "passive"))
      (node (ref "U7") (pin "6") (pinfunction "SCK_6") (pintype "passive"))
    )
    (net (code "40") (name "/TX") (class "Default")
      (node (ref "U5") (pin "10") (pinfunction "PD1/TXD_10") (pintype "passive"))
      (node (ref "U6") (pin "14") (pinfunction "P24_14") (pintype "passive"))
    )
    (net (code "41") (name "/USB_DM") (class "Default")
      (node (ref "P3") (pin "2") (pinfunction "2_2") (pintype "passive"))
      (node (ref "U6") (pin "5") (pinfunction "USBDM_5") (pintype "passive"))
    )
    (net (code "42") (name "/USB_DP") (class "Default")
      (node (ref "P3") (pin "3") (pinfunction "3_3") (pintype "passive"))
      (node (ref "U6") (pin "6") (pinfunction "USBDP_6") (pintype "passive"))
    )
    (net (code "43") (name "/VPA") (class "Default")
      (node (ref "C29") (pin "2") (pinfunction "2_2") (pintype "passive"))
      (node (ref "R28") (pin "2") (pinfunction "2_2") (pintype "passive"))
      (node (ref "U9") (pin "8") (pinfunction "VDDA_8") (pintype "passive"))
    )
    (net (code "44") (name "/opt") (class "Default")
      (node (ref "D3") (pin "2") (pinfunction "K_2") (pintype "passive"))
      (node (ref "R22") (pin "2") (pinfunction "2_2") (pintype "passive"))
      (node (ref "U5") (pin "34") (pinfunction "PA3/ADC3_34") (pintype "passive"))
    )
    (net (code "45") (name "3.3V") (class "Default")
      (node (ref "C15") (pin "1") (pinfunction "1_1") (pintype "passive"))
      (node (ref "C18") (pin "2") (pinfunction "2_2") (pintype "passive"))
      (node (ref "C22") (pin "1") (pinfunction "1_1") (pintype "passive"))
      (node (ref "C23") (pin "1") (pinfunction "1_1") (pintype "passive"))
      (node (ref "C24") (pin "1") (pinfunction "1_1") (pintype "passive"))
      (node (ref "C25") (pin "1") (pinfunction "1_1") (pintype "passive"))
      (node (ref "C8") (pin "2") (pinfunction "2_2") (pintype "passive"))
      (node (ref "C9") (pin "1") (pinfunction "1_1") (pintype "passive"))
      (node (ref "J1") (pin "2") (pinfunction "2_2") (pintype "passive"))
      (node (ref "P2") (pin "1") (pinfunction "1_1") (pintype "passive"))
      (node (ref "P4") (pin "2") (pinfunction "2_2") (pintype "passive"))
      (node (ref "P4_1") (pin "11") (pinfunction "11_11") (pintype "passive"))
      (node (ref "R29") (pin "1") (pinfunction "1_1") (pintype "passive"))
      (node (ref "U3") (pin "3") (pinfunction "OUT_3") (pintype "power_in"))
      (node (ref "U4") (pin "1") (pinfunction "VCC2_1") (pintype "power_in"))
      (node (ref "U5") (pin "17") (pinfunction "VCC_17") (pintype "passive"))
      (node (ref "U5") (pin "27") (pinfunction "AVCC_27") (pintype "passive"))
      (node (ref "U5") (pin "29") (pinfunction "AREF_29") (pintype "passive"))
      (node (ref "U5") (pin "38") (pinfunction "VCC_38") (pintype "passive"))
      (node (ref "U5") (pin "5") (pinfunction "VCC_5") (pintype "passive"))
      (node (ref "U6") (pin "11") (pinfunction "3.3V_11") (pintype "passive"))
      (node (ref "U7") (pin "3") (pinfunction "~{WP}_3") (pintype "passive"))
      (node (ref "U7") (pin "7") (pinfunction "~{HOLD}_7") (pintype "passive"))
      (node (ref "U7") (pin "8") (pinfunction "VCC_8") (pintype "passive"))
      (node (ref "U8") (pin "10") (pinfunction "~{RST}_10") (pintype "input"))
      (node (ref "U8") (pin "16") (pinfunction "VDD_16") (pintype "power_in"))
    )
    (net (code "46") (name "5V") (class "Default")
      (node (ref "C10") (pin "2") (pinfunction "2_2") (pintype "passive"))
      (node (ref "C11") (pin "1") (pinfunction "1_1") (pintype "passive"))
      (node (ref "C14") (pin "1") (pinfunction "1_1") (pintype "passive"))
      (node (ref "D3") (pin "1") (pinfunction "A_1") (pintype "passive"))
      (node (ref "D5") (pin "2") (pinfunction "K_2") (pintype "passive"))
      (node (ref "J2") (pin "2") (pinfunction "2_2") (pintype "passive"))
      (node (ref "U2") (pin "3") (pinfunction "OUT_3") (pintype "power_in"))
      (node (ref "U3") (pin "2") (pinfunction "IN_2") (pintype "power_in"))
      (node (ref "U6") (pin "12") (pinfunction "VMCU_12") (pintype "passive"))
    )
    (net (code "47") (name "14V") (class "Default")
      (node (ref "C19") (pin "1") (pinfunction "1_1") (pintype "passive"))
      (node (ref "C21") (pin "1") (pinfunction "1_1") (pintype "passive"))
      (node (ref "C26") (pin "1") (pinfunction "1_1") (pintype "passive"))
      (node (ref "C27") (pin "1") (pinfunction "1_1") (pintype "passive"))
      (node (ref "C28") (pin "1") (pinfunction "1_1") (pintype "passive"))
      (node (ref "C31") (pin "1") (pinfunction "1_1") (pintype "passive"))
      (node (ref "C42") (pin "1") (pinfunction "1_1") (pintype "passive"))
      (node (ref "C6") (pin "1") (pinfunction "1_1") (pintype "passive"))
      (node (ref "C7") (pin "2") (pinfunction "2_2") (pintype "passive"))
      (node (ref "P1") (pin "2") (pinfunction "2_2") (pintype "passive"))
      (node (ref "Q10") (pin "3") (pinfunction "S_3") (pintype "passive"))
      (node (ref "R23") (pin "2") (pinfunction "2_2") (pintype "passive"))
      (node (ref "R28") (pin "1") (pinfunction "1_1") (pintype "passive"))
      (node (ref "U2") (pin "2") (pinfunction "IN_2") (pintype "power_in"))
      (node (ref "U9") (pin "20") (pinfunction "VDDP2_20") (pintype "passive"))
      (node (ref "U9") (pin "29") (pinfunction "VDDP1_29") (pintype "passive"))
    )
    (net (code "48") (name "GND") (class "Default")
      (node (ref "BT1") (pin "2") (pinfunction "-_2") (pintype "passive"))
      (node (ref "C1") (pin "2") (pinfunction "2_2") (pintype "passive"))
      (node (ref "C10") (pin "1") (pinfunction "1_1") (pintype "passive"))
      (node (ref "C11") (pin "2") (pinfunction "2_2") (pintype "passive"))
      (node (ref "C12") (pin "1") (pinfunction "1_1") (pintype "passive"))
      (node (ref "C13") (pin "1") (pinfunction "1_1") (pintype "passive"))
      (node (ref "C14") (pin "2") (pinfunction "2_2") (pintype "passive"))
      (node (ref "C15") (pin "2") (pinfunction "2_2") (pintype "passive"))
      (node (ref "C17") (pin "2") (pinfunction "2_2") (pintype "passive"))
      (node (ref "C18") (pin "1") (pinfunction "1_1") (pintype "passive"))
      (node (ref "C19") (pin "2") (pinfunction "2_2") (pintype "passive"))
      (node (ref "C2") (pin "1") (pinfunction "1_1") (pintype "passive"))
      (node (ref "C20") (pin "2") (pinfunction "2_2") (pintype "passive"))
      (node (ref "C21") (pin "2") (pinfunction "2_2") (pintype "passive"))
      (node (ref "C22") (pin "2") (pinfunction "2_2") (pintype "passive"))
      (node (ref "C23") (pin "2") (pinfunction "2_2") (pintype "passive"))
      (node (ref "C24") (pin "2") (pinfunction "2_2") (pintype "passive"))
      (node (ref "C25") (pin "2") (pinfunction "2_2") (pintype "passive"))
      (node (ref "C26") (pin "2") (pinfunction "2_2") (pintype "passive"))
      (node (ref "C27") (pin "2") (pinfunction "2_2") (pintype "passive"))
      (node (ref "C28") (pin "2") (pinfunction "2_2") (pintype "passive"))
      (node (ref "C29") (pin "1") (pinfunction "1_1") (pintype "passive"))
      (node (ref "C3") (pin "1") (pinfunction "1_1") (pintype "passive"))
      (node (ref "C30") (pin "1") (pinfunction "1_1") (pintype "passive"))
      (node (ref "C31") (pin "2") (pinfunction "2_2") (pintype "passive"))
      (node (ref "C33") (pin "2") (pinfunction "2_2") (pintype "passive"))
      (node (ref "C35") (pin "1") (pinfunction "1_1") (pintype "passive"))
      (node (ref "C36") (pin "1") (pinfunction "1_1") (pintype "passive"))
      (node (ref "C37") (pin "2") (pinfunction "2_2") (pintype "passive"))
      (node (ref "C38") (pin "1") (pinfunction "1_1") (pintype "passive"))
      (node (ref "C39") (pin "1") (pinfunction "1_1") (pintype "passive"))
      (node (ref "C4") (pin "1") (pinfunction "1_1") (pintype "passive"))
      (node (ref "C41") (pin "2") (pinfunction "2_2") (pintype "passive"))
      (node (ref "C42") (pin "2") (pinfunction "2_2") (pintype "passive"))
      (node (ref "C43") (pin "1") (pinfunction "1_1") (pintype "passive"))
      (node (ref "C44") (pin "1") (pinfunction "1_1") (pintype "passive"))
      (node (ref "C45") (pin "1") (pinfunction "1_1") (pintype "passive"))
      (node (ref "C46") (pin "1") (pinfunction "1_1") (pintype "passive"))
      (node (ref "C48") (pin "2") (pinfunction "2_2") (pintype "passive"))
      (node (ref "C49") (pin "1") (pinfunction "1_1") (pintype "passive"))
      (node (ref "C5") (pin "1") (pinfunction "1_1") (pintype "passive"))
      (node (ref "C6") (pin "2") (pinfunction "2_2") (pintype "passive"))
      (node (ref "C7") (pin "1") (pinfunction "1_1") (pintype "passive"))
      (node (ref "C8") (pin "1") (pinfunction "1_1") (pintype "passive"))
      (node (ref "C9") (pin "2") (pinfunction "2_2") (pintype "passive"))
      (node (ref "J1") (pin "1") (pinfunction "1_1") (pintype "passive"))
      (node (ref "J2") (pin "6") (pinfunction "6_6") (pintype "passive"))
      (node (ref "P1") (pin "1") (pinfunction "1_1") (pintype "passive"))
      (node (ref "P2") (pin "8") (pinfunction "8_8") (pintype "passive"))
      (node (ref "P3") (pin "4") (pinfunction "4_4") (pintype "passive"))
      (node (ref "P4_1") (pin "2") (pinfunction "2_2") (pintype "passive"))
      (node (ref "P4_1") (pin "3") (pinfunction "3_3") (pintype "passive"))
      (node (ref "P4_1") (pin "4") (pinfunction "4_4") (pintype "passive"))
      (node (ref "P4_1") (pin "5") (pinfunction "5_5") (pintype "passive"))
      (node (ref "Q1") (pin "1") (pinfunction "E_1") (pintype "passive"))
      (node (ref "Q11") (pin "1") (pinfunction "E_1") (pintype "passive"))
      (node (ref "Q6") (pin "2") (pinfunction "E_2") (pintype "passive"))
      (node (ref "Q7") (pin "2") (pinfunction "E_2") (pintype "passive"))
      (node (ref "Q8") (pin "2") (pinfunction "E_2") (pintype "passive"))
      (node (ref "Q9") (pin "2") (pinfunction "E_2") (pintype "passive"))
      (node (ref "R22") (pin "1") (pinfunction "1_1") (pintype "passive"))
      (node (ref "R33") (pin "2") (pinfunction "2_2") (pintype "passive"))
      (node (ref "S1") (pin "2") (pinfunction "2_2") (pintype "passive"))
      (node (ref "U1") (pin "8") (pinfunction "GND_8") (pintype "power_in"))
      (node (ref "U2") (pin "1") (pinfunction "GND_1") (pintype "power_in"))
      (node (ref "U3") (pin "1") (pinfunction "GND_1") (pintype "power_in"))
      (node (ref "U4") (pin "4") (pinfunction "GND_4") (pintype "power_in"))
      (node (ref "U5") (pin "18") (pinfunction "GND_18") (pintype "passive"))
      (node (ref "U5") (pin "28") (pinfunction "GND_28") (pintype "passive"))
      (node (ref "U5") (pin "39") (pinfunction "GND_39") (pintype "passive"))
      (node (ref "U5") (pin "6") (pinfunction "GND_6") (pintype "passive"))
      (node (ref "U6") (pin "13") (pinfunction "GND_13") (pintype "passive"))
      (node (ref "U6") (pin "8") (pinfunction "AGND_8") (pintype "passive"))
      (node (ref "U7") (pin "4") (pinfunction "GND_4") (pintype "passive"))
      (node (ref "U8") (pin "13") (pinfunction "~{OE}_13") (pintype "input"))
      (node (ref "U8") (pin "8") (pinfunction "GND_8") (pintype "power_in"))
      (node (ref "U9") (pin "1") (pinfunction "VSSD_1") (pintype "passive"))
      (node (ref "U9") (pin "16") (pinfunction "VSSD_16") (pintype "passive"))
      (node (ref "U9") (pin "17") (pinfunction "VSSD_17") (pintype "passive"))
      (node (ref "U9") (pin "23") (pinfunction "VSSP2_23") (pintype "passive"))
      (node (ref "U9") (pin "26") (pinfunction "VSSP1_26") (pintype "passive"))
      (node (ref "U9") (pin "32") (pinfunction "VSSD_32") (pintype "passive"))
      (node (ref "U9") (pin "7") (pinfunction "CGND_7") (pintype "passive"))
      (node (ref "U9") (pin "9") (pinfunction "VSSA_9") (pintype "passive"))
    )
    (net (code "49") (name "Net-(BT1-+)") (class "Default")
      (node (ref "BT1") (pin "1") (pinfunction "+_1") (pintype "passive"))
      (node (ref "R26") (pin "2") (pinfunction "2_2") (pintype "passive"))
      (node (ref "U4") (pin "8") (pinfunction "VCC1_8") (pintype "power_in"))
    )
    (net (code "50") (name "Net-(C33-Pad1)") (class "Default")
      (node (ref "C33") (pin "1") (pinfunction "1_1") (pintype "passive"))
      (node (ref "L1") (pin "2") (pinfunction "2_2") (pintype "passive"))
      (node (ref "LS1") (pin "1") (pinfunction "1_1") (pintype "passive"))
      (node (ref "LS2") (pin "2") (pinfunction "2_2") (pintype "passive"))
    )
    (net (code "51") (name "Net-(C37-Pad1)") (class "Default")
      (node (ref "C37") (pin "1") (pinfunction "1_1") (pintype "passive"))
      (node (ref "R32") (pin "2") (pinfunction "2_2") (pintype "passive"))
    )
    (net (code "52") (name "Net-(C41-Pad1)") (class "Default")
      (node (ref "C41") (pin "1") (pinfunction "1_1") (pintype "passive"))
      (node (ref "R34") (pin "2") (pinfunction "2_2") (pintype "passive"))
    )
    (net (code "53") (name "Net-(C44-Pad2)") (class "Default")
      (node (ref "C44") (pin "2") (pinfunction "2_2") (pintype "passive"))
      (node (ref "L2") (pin "2") (pinfunction "2_2") (pintype "passive"))
      (node (ref "LS1") (pin "2") (pinfunction "2_2") (pintype "passive"))
      (node (ref "LS2") (pin "1") (pinfunction "1_1") (pintype "passive"))
    )
    (net (code "54") (name "Net-(D1-A)") (class "Default")
      (node (ref "D1") (pin "1") (pinfunction "A_1") (pintype "passive"))
      (node (ref "D2") (pin "2") (pinfunction "K_2") (pintype "passive"))
    )
    (net (code "55") (name "Net-(D1-K)") (class "Default")
      (node (ref "D1") (pin "2") (pinfunction "K_2") (pintype "passive"))
      (node (ref "R1") (pin "1") (pinfunction "1_1") (pintype "passive"))
    )
    (net (code "56") (name "Net-(D4-K)") (class "Default")
      (node (ref "C16") (pin "1") (pinfunction "1_1") (pintype "passive"))
      (node (ref "D4") (pin "2") (pinfunction "K_2") (pintype "passive"))
      (node (ref "R27") (pin "2") (pinfunction "2_2") (pintype "passive"))
    )
    (net (code "57") (name "Net-(D5-A)") (class "Default")
      (node (ref "D5") (pin "1") (pinfunction "A_1") (pintype "passive"))
      (node (ref "P3") (pin "1") (pinfunction "1_1") (pintype "passive"))
    )
    (net (code "58") (name "Net-(Q1-B)") (class "Default")
      (node (ref "Q1") (pin "2") (pinfunction "B_2") (pintype "passive"))
      (node (ref "R2") (pin "2") (pinfunction "2_2") (pintype "passive"))
    )
    (net (code "59") (name "Net-(Q1-C)") (class "Default")
      (node (ref "Q1") (pin "3") (pinfunction "C_3") (pintype "passive"))
      (node (ref "R1") (pin "2") (pinfunction "2_2") (pintype "passive"))
    )
    (net (code "60") (name "Net-(Q2-D)") (class "Default")
      (node (ref "C2") (pin "2") (pinfunction "2_2") (pintype "passive"))
      (node (ref "DS2") (pin "1") (pinfunction "A_1") (pintype "passive"))
      (node (ref "DS2") (pin "8") (pinfunction "A_8") (pintype "passive"))
      (node (ref "Q2") (pin "3") (pinfunction "D_3") (pintype "passive"))
    )
    (net (code "61") (name "Net-(Q2-G)") (class "Default")
      (node (ref "Q2") (pin "1") (pinfunction "G_1") (pintype "passive"))
      (node (ref "R12") (pin "1") (pinfunction "1_1") (pintype "passive"))
      (node (ref "R7") (pin "2") (pinfunction "2_2") (pintype "passive"))
    )
    (net (code "62") (name "Net-(Q3-D)") (class "Default")
      (node (ref "C3") (pin "2") (pinfunction "2_2") (pintype "passive"))
      (node (ref "DS2") (pin "11") (pinfunction "A_11") (pintype "passive"))
      (node (ref "DS2") (pin "18") (pinfunction "A_18") (pintype "passive"))
      (node (ref "Q3") (pin "3") (pinfunction "D_3") (pintype "passive"))
    )
    (net (code "63") (name "Net-(Q3-G)") (class "Default")
      (node (ref "Q3") (pin "1") (pinfunction "G_1") (pintype "passive"))
      (node (ref "R13") (pin "1") (pinfunction "1_1") (pintype "passive"))
      (node (ref "R8") (pin "2") (pinfunction "2_2") (pintype "passive"))
    )
    (net (code "64") (name "Net-(Q4-D)") (class "Default")
      (node (ref "C4") (pin "2") (pinfunction "2_2") (pintype "passive"))
      (node (ref "DS1") (pin "1") (pinfunction "A_1") (pintype "passive"))
      (node (ref "DS1") (pin "8") (pinfunction "A_8") (pintype "passive"))
      (node (ref "Q4") (pin "3") (pinfunction "D_3") (pintype "passive"))
    )
    (net (code "65") (name "Net-(Q4-G)") (class "Default")
      (node (ref "Q4") (pin "1") (pinfunction "G_1") (pintype "passive"))
      (node (ref "R10") (pin "2") (pinfunction "2_2") (pintype "passive"))
      (node (ref "R15") (pin "1") (pinfunction "1_1") (pintype "passive"))
    )
    (net (code "66") (name "Net-(Q5-D)") (class "Default")
      (node (ref "C5") (pin "2") (pinfunction "2_2") (pintype "passive"))
      (node (ref "DS1") (pin "11") (pinfunction "A_11") (pintype "passive"))
      (node (ref "DS1") (pin "18") (pinfunction "A_18") (pintype "passive"))
      (node (ref "Q5") (pin "3") (pinfunction "D_3") (pintype "passive"))
    )
    (net (code "67") (name "Net-(Q5-G)") (class "Default")
      (node (ref "Q5") (pin "1") (pinfunction "G_1") (pintype "passive"))
      (node (ref "R11") (pin "2") (pinfunction "2_2") (pintype "passive"))
      (node (ref "R16") (pin "1") (pinfunction "1_1") (pintype "passive"))
    )
    (net (code "68") (name "Net-(Q6-B)") (class "Default")
      (node (ref "Q6") (pin "1") (pinfunction "B_1") (pintype "passive"))
      (node (ref "R18") (pin "1") (pinfunction "1_1") (pintype "passive"))
    )
    (net (code "69") (name "Net-(Q6-C)") (class "Default")
      (node (ref "Q6") (pin "3") (pinfunction "C_3") (pintype "passive"))
      (node (ref "R12") (pin "2") (pinfunction "2_2") (pintype "passive"))
    )
    (net (code "70") (name "Net-(Q7-B)") (class "Default")
      (node (ref "Q7") (pin "1") (pinfunction "B_1") (pintype "passive"))
      (node (ref "R19") (pin "1") (pinfunction "1_1") (pintype "passive"))
    )
    (net (code "71") (name "Net-(Q7-C)") (class "Default")
      (node (ref "Q7") (pin "3") (pinfunction "C_3") (pintype "passive"))
      (node (ref "R13") (pin "2") (pinfunction "2_2") (pintype "passive"))
    )
    (net (code "72") (name "Net-(Q8-B)") (class "Default")
      (node (ref "Q8") (pin "1") (pinfunction "B_1") (pintype "passive"))
      (node (ref "R20") (pin "1") (pinfunction "1_1") (pintype "passive"))
    )
    (net (code "73") (name "Net-(Q8-C)") (class "Default")
      (node (ref "Q8") (pin "3") (pinfunction "C_3") (pintype "passive"))
      (node (ref "R15") (pin "2") (pinfunction "2_2") (pintype "passive"))
    )
    (net (code "74") (name "Net-(Q9-B)") (class "Default")
      (node (ref "Q9") (pin "1") (pinfunction "B_1") (pintype "passive"))
      (node (ref "R21") (pin "1") (pinfunction "1_1") (pintype "passive"))
    )
    (net (code "75") (name "Net-(Q9-C)") (class "Default")
      (node (ref "Q9") (pin "3") (pinfunction "C_3") (pintype "passive"))
      (node (ref "R16") (pin "2") (pinfunction "2_2") (pintype "passive"))
    )
    (net (code "76") (name "Net-(Q10-G)") (class "Default")
      (node (ref "Q10") (pin "1") (pinfunction "G_1") (pintype "passive"))
      (node (ref "R23") (pin "1") (pinfunction "1_1") (pintype "passive"))
      (node (ref "R25") (pin "2") (pinfunction "2_2") (pintype "passive"))
    )
    (net (code "77") (name "Net-(Q11-B)") (class "Default")
      (node (ref "Q11") (pin "2") (pinfunction "B_2") (pintype "passive"))
      (node (ref "R27") (pin "1") (pinfunction "1_1") (pintype "passive"))
    )
    (net (code "78") (name "Net-(Q11-C)") (class "Default")
      (node (ref "Q11") (pin "3") (pinfunction "C_3") (pintype "passive"))
      (node (ref "R25") (pin "1") (pinfunction "1_1") (pintype "passive"))
    )
    (net (code "79") (name "Net-(U1-IN1)") (class "Default")
      (node (ref "U1") (pin "1") (pinfunction "IN1_1") (pintype "input"))
      (node (ref "U8") (pin "6") (pinfunction "QG_6") (pintype "tri_state"))
    )
    (net (code "80") (name "Net-(U1-IN2)") (class "Default")
      (node (ref "U1") (pin "2") (pinfunction "IN2_2") (pintype "input"))
      (node (ref "U8") (pin "5") (pinfunction "QF_5") (pintype "tri_state"))
    )
    (net (code "81") (name "Net-(U1-IN3)") (class "Default")
      (node (ref "U1") (pin "3") (pinfunction "IN3_3") (pintype "input"))
      (node (ref "U8") (pin "4") (pinfunction "QE_4") (pintype "tri_state"))
    )
    (net (code "82") (name "Net-(U1-IN4)") (class "Default")
      (node (ref "U1") (pin "4") (pinfunction "IN4_4") (pintype "input"))
      (node (ref "U8") (pin "3") (pinfunction "QD_3") (pintype "tri_state"))
    )
    (net (code "83") (name "Net-(U1-IN5)") (class "Default")
      (node (ref "U1") (pin "5") (pinfunction "IN5_5") (pintype "input"))
      (node (ref "U8") (pin "2") (pinfunction "QC_2") (pintype "tri_state"))
    )
    (net (code "84") (name "Net-(U1-IN6)") (class "Default")
      (node (ref "U1") (pin "6") (pinfunction "IN6_6") (pintype "input"))
      (node (ref "U8") (pin "1") (pinfunction "QB_1") (pintype "tri_state"))
    )
    (net (code "85") (name "Net-(U1-IN7)") (class "Default")
      (node (ref "U1") (pin "7") (pinfunction "IN7_7") (pintype "input"))
      (node (ref "U8") (pin "15") (pinfunction "QA_15") (pintype "tri_state"))
    )
    (net (code "86") (name "Net-(U1-OUT1)") (class "Default")
      (node (ref "R17") (pin "2") (pinfunction "2_2") (pintype "passive"))
      (node (ref "U1") (pin "16") (pinfunction "OUT1_16") (pintype "open_collector"))
    )
    (net (code "87") (name "Net-(U1-OUT2)") (class "Default")
      (node (ref "R14") (pin "2") (pinfunction "2_2") (pintype "passive"))
      (node (ref "U1") (pin "15") (pinfunction "OUT2_15") (pintype "open_collector"))
    )
    (net (code "88") (name "Net-(U1-OUT3)") (class "Default")
      (node (ref "R9") (pin "2") (pinfunction "2_2") (pintype "passive"))
      (node (ref "U1") (pin "14") (pinfunction "OUT3_14") (pintype "open_collector"))
    )
    (net (code "89") (name "Net-(U1-OUT4)") (class "Default")
      (node (ref "R6") (pin "2") (pinfunction "2_2") (pintype "passive"))
      (node (ref "U1") (pin "13") (pinfunction "OUT4_13") (pintype "open_collector"))
    )
    (net (code "90") (name "Net-(U1-OUT5)") (class "Default")
      (node (ref "R5") (pin "2") (pinfunction "2_2") (pintype "passive"))
      (node (ref "U1") (pin "12") (pinfunction "OUT5_12") (pintype "open_collector"))
    )
    (net (code "91") (name "Net-(U1-OUT6)") (class "Default")
      (node (ref "R4") (pin "2") (pinfunction "2_2") (pintype "passive"))
      (node (ref "U1") (pin "11") (pinfunction "OUT6_11") (pintype "open_collector"))
    )
    (net (code "92") (name "Net-(U1-OUT7)") (class "Default")
      (node (ref "R3") (pin "2") (pinfunction "2_2") (pintype "passive"))
      (node (ref "U1") (pin "10") (pinfunction "OUT7_10") (pintype "open_collector"))
    )
    (net (code "93") (name "Net-(U4-X1)") (class "Default")
      (node (ref "C12") (pin "2") (pinfunction "2_2") (pintype "passive"))
      (node (ref "U4") (pin "2") (pinfunction "X1_2") (pintype "input"))
      (node (ref "Y1") (pin "2") (pinfunction "OSC2_2") (pintype "passive"))
    )
    (net (code "94") (name "Net-(U4-X2)") (class "Default")
      (node (ref "C13") (pin "2") (pinfunction "2_2") (pintype "passive"))
      (node (ref "U4") (pin "3") (pinfunction "X2_3") (pintype "input"))
      (node (ref "Y1") (pin "1") (pinfunction "OSC1_1") (pintype "passive"))
    )
    (net (code "95") (name "Net-(U6-VCOM)") (class "Default")
      (node (ref "C17") (pin "1") (pinfunction "1_1") (pintype "passive"))
      (node (ref "U6") (pin "7") (pinfunction "VCOM_7") (pintype "passive"))
    )
    (net (code "96") (name "Net-(U9-BOOT1)") (class "Default")
      (node (ref "C34") (pin "2") (pinfunction "2_2") (pintype "passive"))
      (node (ref "U9") (pin "28") (pinfunction "BOOT1_28") (pintype "passive"))
    )
    (net (code "97") (name "Net-(U9-BOOT2)") (class "Default")
      (node (ref "C40") (pin "2") (pinfunction "2_2") (pintype "passive"))
      (node (ref "U9") (pin "21") (pinfunction "BOOT2_21") (pintype "passive"))
    )
    (net (code "98") (name "Net-(U9-DREF)") (class "Default")
      (node (ref "C43") (pin "2") (pinfunction "2_2") (pintype "passive"))
      (node (ref "U9") (pin "18") (pinfunction "DREF_18") (pintype "passive"))
    )
    (net (code "99") (name "Net-(U9-HVP1)") (class "Default")
      (node (ref "C48") (pin "1") (pinfunction "1_1") (pintype "passive"))
      (node (ref "R30") (pin "2") (pinfunction "2_2") (pintype "passive"))
      (node (ref "U9") (pin "30") (pinfunction "HVP1_30") (pintype "passive"))
    )
    (net (code "100") (name "Net-(U9-HVP2)") (class "Default")
      (node (ref "C49") (pin "2") (pinfunction "2_2") (pintype "passive"))
      (node (ref "R31") (pin "2") (pinfunction "2_2") (pintype "passive"))
      (node (ref "U9") (pin "19") (pinfunction "HVP2_19") (pintype "passive"))
    )
    (net (code "101") (name "Net-(U9-HVPREF)") (class "Default")
      (node (ref "C45") (pin "2") (pinfunction "2_2") (pintype "passive"))
      (node (ref "R30") (pin "1") (pinfunction "1_1") (pintype "passive"))
      (node (ref "R31") (pin "1") (pinfunction "1_1") (pintype "passive"))
      (node (ref "U9") (pin "11") (pinfunction "HVPREF_11") (pintype "passive"))
    )
    (net (code "102") (name "Net-(U9-IN1N)") (class "Default")
      (node (ref "C32") (pin "2") (pinfunction "2_2") (pintype "passive"))
      (node (ref "U9") (pin "15") (pinfunction "IN2P_15") (pintype "passive"))
      (node (ref "U9") (pin "3") (pinfunction "IN1N_3") (pintype "passive"))
    )
    (net (code "103") (name "Net-(U9-IN1P)") (class "Default")
      (node (ref "C30") (pin "2") (pinfunction "2_2") (pintype "passive"))
      (node (ref "U9") (pin "14") (pinfunction "IN2N_14") (pintype "passive"))
      (node (ref "U9") (pin "2") (pinfunction "IN1P_2") (pintype "passive"))
    )
    (net (code "104") (name "Net-(U9-INREF)") (class "Default")
      (node (ref "C46") (pin "2") (pinfunction "2_2") (pintype "passive"))
      (node (ref "U9") (pin "12") (pinfunction "INREF_12") (pintype "passive"))
    )
    (net (code "105") (name "Net-(U9-OSCREF)") (class "Default")
      (node (ref "C35") (pin "2") (pinfunction "2_2") (pintype "passive"))
      (node (ref "R33") (pin "1") (pinfunction "1_1") (pintype "passive"))
      (node (ref "U9") (pin "10") (pinfunction "OSCREF_10") (pintype "passive"))
    )
    (net (code "106") (name "Net-(U9-OUT1)") (class "Default")
      (node (ref "C34") (pin "1") (pinfunction "1_1") (pintype "passive"))
      (node (ref "L1") (pin "1") (pinfunction "1_1") (pintype "passive"))
      (node (ref "R32") (pin "1") (pinfunction "1_1") (pintype "passive"))
      (node (ref "U9") (pin "27") (pinfunction "OUT1_27") (pintype "passive"))
    )
    (net (code "107") (name "Net-(U9-OUT2)") (class "Default")
      (node (ref "C40") (pin "1") (pinfunction "1_1") (pintype "passive"))
      (node (ref "L2") (pin "1") (pinfunction "1_1") (pintype "passive"))
      (node (ref "R34") (pin "1") (pinfunction "1_1") (pintype "passive"))
      (node (ref "U9") (pin "22") (pinfunction "OUT2_22") (pintype "passive"))
    )
    (net (code "108") (name "Net-(U9-STAB1)") (class "Default")
      (node (ref "C36") (pin "2") (pinfunction "2_2") (pintype "passive"))
      (node (ref "U9") (pin "24") (pinfunction "STAB2_24") (pintype "passive"))
      (node (ref "U9") (pin "25") (pinfunction "STAB1_25") (pintype "passive"))
    )
    (net (code "109") (name "PWM") (class "Default")
      (node (ref "C1") (pin "1") (pinfunction "1_1") (pintype "passive"))
      (node (ref "D2") (pin "1") (pinfunction "A_1") (pintype "passive"))
      (node (ref "P4") (pin "1") (pinfunction "1_1") (pintype "passive"))
      (node (ref "P4_1") (pin "12") (pinfunction "12_12") (pintype "passive"))
      (node (ref "Q10") (pin "2") (pinfunction "D_2") (pintype "passive"))
      (node (ref "Q2") (pin "2") (pinfunction "S_2") (pintype "passive"))
      (node (ref "Q3") (pin "2") (pinfunction "S_2") (pintype "passive"))
      (node (ref "Q4") (pin "2") (pinfunction "S_2") (pintype "passive"))
      (node (ref "Q5") (pin "2") (pinfunction "S_2") (pintype "passive"))
      (node (ref "R10") (pin "1") (pinfunction "1_1") (pintype "passive"))
      (node (ref "R11") (pin "1") (pinfunction "1_1") (pintype "passive"))
      (node (ref "R7") (pin "1") (pinfunction "1_1") (pintype "passive"))
      (node (ref "R8") (pin "1") (pinfunction "1_1") (pintype "passive"))
      (node (ref "U1") (pin "9") (pinfunction "COM_9") (pintype "passive"))
    )
    (net (code "110") (name "unconnected-(DS1-DP-Pad5)") (class "Default")
      (node (ref "DS1") (pin "5") (pinfunction "DP_5") (pintype "passive"))
    )
    (net (code "111") (name "unconnected-(DS1-DP-Pad15)") (class "Default")
      (node (ref "DS1") (pin "15") (pinfunction "DP_15") (pintype "passive"))
    )
    (net (code "112") (name "unconnected-(DS2-DP-Pad5)") (class "Default")
      (node (ref "DS2") (pin "5") (pinfunction "DP_5") (pintype "passive"))
    )
    (net (code "113") (name "unconnected-(DS2-DP-Pad15)") (class "Default")
      (node (ref "DS2") (pin "15") (pinfunction "DP_15") (pintype "passive"))
    )
    (net (code "114") (name "unconnected-(U5-PA0{slash}ADC0-Pad37)") (class "Default")
      (node (ref "U5") (pin "37") (pinfunction "PA0/ADC0_37") (pintype "passive"))
    )
    (net (code "115") (name "unconnected-(U5-PA1{slash}ADC1-Pad36)") (class "Default")
      (node (ref "U5") (pin "36") (pinfunction "PA1/ADC1_36") (pintype "passive"))
    )
    (net (code "116") (name "unconnected-(U5-PB0{slash}XCK{slash}T0-Pad40)") (class "Default")
      (node (ref "U5") (pin "40") (pinfunction "PB0/XCK/T0_40") (pintype "passive"))
    )
    (net (code "117") (name "unconnected-(U5-PB1{slash}T1-Pad41)") (class "Default")
      (node (ref "U5") (pin "41") (pinfunction "PB1/T1_41") (pintype "passive"))
    )
    (net (code "118") (name "unconnected-(U5-PD6{slash}ICP1-Pad15)") (class "Default")
      (node (ref "U5") (pin "15") (pinfunction "PD6/ICP1_15") (pintype "passive"))
    )
    (net (code "119") (name "unconnected-(U5-XTAL1-Pad8)") (class "Default")
      (node (ref "U5") (pin "8") (pinfunction "XTAL1_8") (pintype "passive"))
    )
    (net (code "120") (name "unconnected-(U5-XTAL2-Pad7)") (class "Default")
      (node (ref "U5") (pin "7") (pinfunction "XTAL2_7") (pintype "passive"))
    )
    (net (code "121") (name "unconnected-(U6-VPP-Pad16)") (class "Default")
      (node (ref "U6") (pin "16") (pinfunction "VPP_16") (pintype "passive"))
    )
    (net (code "122") (name "unconnected-(U8-QH-Pad7)") (class "Default")
      (node (ref "U8") (pin "7") (pinfunction "QH_7") (pintype "tri_state"))
    )
    (net (code "123") (name "unconnected-(U8-SDO-Pad9)") (class "Default")
      (node (ref "U8") (pin "9") (pinfunction "SDO_9") (pintype "output"))
    )
    (net (code "124") (name "unconnected-(U9-DIAG-Pad4)") (class "Default")
      (node (ref "U9") (pin "4") (pinfunction "DIAG_4") (pintype "passive"))
    )
    (net (code "125") (name "unconnected-(U9-OSCIO-Pad31)") (class "Default")
      (node (ref "U9") (pin "31") (pinfunction "OSCIO_31") (pintype "passive"))
    )
    (net (code "126") (name "unconnected-(U9-TEST-Pad13)") (class "Default")
      (node (ref "U9") (pin "13") (pinfunction "TEST_13") (pintype "passive"))
    )
  )
)
